# no.net
KiCad netlist of a schematic drawn in Altium Designer
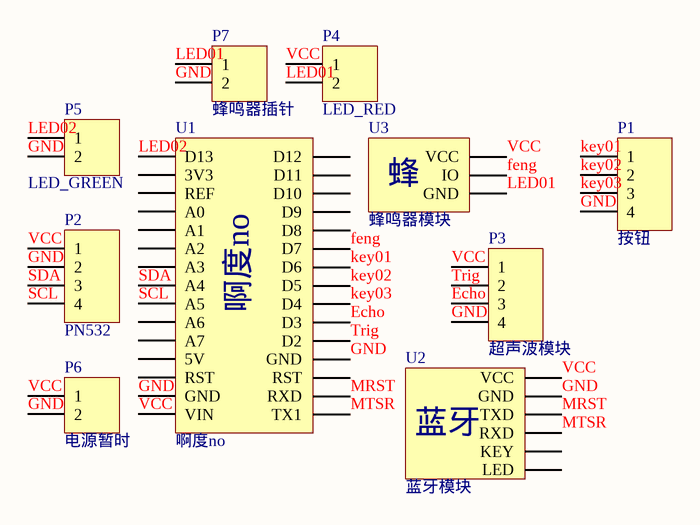
[diagram p0: 啊度no.SchDoc]

(export (version "E")
  (design (tool "Eeschema 10.0.6"))
  (components
    (comp (ref "P1")
      (value "按钮")
      (footprint "HDR1X4")
      (description "Header, 4-Pin")
      (fields (field (name "PUBLISHER") "Altium Limited"))
      (libsource (lib "Miscellaneous Connectors") (part "Header 4"))
    )
    (comp (ref "P2")
      (value "PN532")
      (footprint "HDR1X4")
      (description "Header, 4-Pin")
      (fields (field (name "PUBLISHER") "Altium Limited"))
      (libsource (lib "Miscellaneous Connectors") (part "Header 4"))
    )
    (comp (ref "P3")
      (value "超声波模块")
      (footprint "HDR1X4")
      (description "Header, 4-Pin")
      (fields (field (name "PUBLISHER") "Altium Limited"))
      (libsource (lib "Miscellaneous Connectors") (part "Header 4"))
    )
    (comp (ref "P4")
      (value "LED_RED")
      (footprint "HDR1X2")
      (description "Header, 2-Pin")
      (fields (field (name "PUBLISHER") "Altium Limited"))
      (libsource (lib "Miscellaneous Connectors") (part "Header 2"))
    )
    (comp (ref "P5")
      (value "LED_GREEN")
      (footprint "HDR1X2")
      (description "Header, 2-Pin")
      (fields (field (name "PUBLISHER") "Altium Limited"))
      (libsource (lib "Miscellaneous Connectors") (part "Header 2"))
    )
    (comp (ref "P6")
      (value "电源暂时")
      (footprint "HDR1X2")
      (description "Header, 2-Pin")
      (fields (field (name "PUBLISHER") "Altium Limited"))
      (libsource (lib "Miscellaneous Connectors") (part "Header 2"))
    )
    (comp (ref "P7")
      (value "蜂鸣器插针")
      (footprint "HDR1X2")
      (description "Header, 2-Pin")
      (fields (field (name "PUBLISHER") "Altium Limited"))
      (libsource (lib "Miscellaneous Connectors") (part "Header 2"))
    )
    (comp (ref "U1") (value "啊度no") (footprint "啊度no") (libsource (lib "元件库编号001") (part "啊度no")))
    (comp (ref "U2") (value "蓝牙模块") (footprint "蓝牙模块") (libsource (lib "元件库编号001") (part "蓝牙模块")))
    (comp (ref "U3") (value "蜂鸣器模块") (footprint "蜂鸣器模块") (libsource (lib "元件库编号001") (part "蜂鸣器模块")))
  )
  (nets
    (net (code "1") (name "/Echo") (class "Default")
      (node (ref "P3") (pin "3") (pinfunction "3_3") (pintype "passive"))
      (node (ref "U1") (pin "D3") (pinfunction "D3_D3") (pintype "passive"))
    )
    (net (code "2") (name "/GND") (class "Default")
      (node (ref "P1") (pin "4") (pinfunction "4_4") (pintype "passive"))
      (node (ref "P2") (pin "2") (pinfunction "2_2") (pintype "passive"))
      (node (ref "P3") (pin "4") (pinfunction "4_4") (pintype "passive"))
      (node (ref "P5") (pin "2") (pinfunction "2_2") (pintype "passive"))
      (node (ref "P6") (pin "2") (pinfunction "2_2") (pintype "passive"))
      (node (ref "P7") (pin "2") (pinfunction "2_2") (pintype "passive"))
      (node (ref "U1") (pin "GND") (pinfunction "GND_GND") (pintype "passive"))
      (node (ref "U2") (pin "GND") (pinfunction "GND_GND") (pintype "passive"))
    )
    (net (code "3") (name "/LED01") (class "Default")
      (node (ref "P4") (pin "2") (pinfunction "2_2") (pintype "passive"))
      (node (ref "P7") (pin "1") (pinfunction "1_1") (pintype "passive"))
      (node (ref "U3") (pin "GND") (pinfunction "GND_GND") (pintype "passive"))
    )
    (net (code "4") (name "/LED02") (class "Default")
      (node (ref "P5") (pin "1") (pinfunction "1_1") (pintype "passive"))
      (node (ref "U1") (pin "D13") (pinfunction "D13_D13") (pintype "passive"))
    )
    (net (code "5") (name "/MRST") (class "Default")
      (node (ref "U1") (pin "RXD") (pinfunction "RXD_RXD") (pintype "passive"))
      (node (ref "U2") (pin "TXD") (pinfunction "TXD_TXD") (pintype "passive"))
    )
    (net (code "6") (name "/MTSR") (class "Default")
      (node (ref "U1") (pin "TX1") (pinfunction "TX1_TX1") (pintype "passive"))
      (node (ref "U2") (pin "RXD") (pinfunction "RXD_RXD") (pintype "passive"))
    )
    (net (code "7") (name "/SCL") (class "Default")
      (node (ref "P2") (pin "4") (pinfunction "4_4") (pintype "passive"))
      (node (ref "U1") (pin "A5") (pinfunction "A5_A5") (pintype "passive"))
    )
    (net (code "8") (name "/SDA") (class "Default")
      (node (ref "P2") (pin "3") (pinfunction "3_3") (pintype "passive"))
      (node (ref "U1") (pin "A4") (pinfunction "A4_A4") (pintype "passive"))
    )
    (net (code "9") (name "/Trig") (class "Default")
      (node (ref "P3") (pin "2") (pinfunction "2_2") (pintype "passive"))
      (node (ref "U1") (pin "D2") (pinfunction "D2_D2") (pintype "passive"))
    )
    (net (code "10") (name "/VCC") (class "Default")
      (node (ref "P2") (pin "1") (pinfunction "1_1") (pintype "passive"))
      (node (ref "P3") (pin "1") (pinfunction "1_1") (pintype "passive"))
      (node (ref "P4") (pin "1") (pinfunction "1_1") (pintype "passive"))
      (node (ref "P6") (pin "1") (pinfunction "1_1") (pintype "passive"))
      (node (ref "U1") (pin "VIN") (pinfunction "VIN_VIN") (pintype "passive"))
      (node (ref "U2") (pin "VCC") (pinfunction "VCC_VCC") (pintype "passive"))
      (node (ref "U3") (pin "VCC") (pinfunction "VCC_VCC") (pintype "passive"))
    )
    (net (code "11") (name "/feng") (class "Default")
      (node (ref "U1") (pin "D7") (pinfunction "D7_D7") (pintype "passive"))
      (node (ref "U3") (pin "IO") (pinfunction "IO_IO") (pintype "passive"))
    )
    (net (code "12") (name "/key01") (class "Default")
      (node (ref "P1") (pin "1") (pinfunction "1_1") (pintype "passive"))
      (node (ref "U1") (pin "D6") (pinfunction "D6_D6") (pintype "passive"))
    )
    (net (code "13") (name "/key02") (class "Default")
      (node (ref "P1") (pin "2") (pinfunction "2_2") (pintype "passive"))
      (node (ref "U1") (pin "D5") (pinfunction "D5_D5") (pintype "passive"))
    )
    (net (code "14") (name "/key03") (class "Default")
      (node (ref "P1") (pin "3") (pinfunction "3_3") (pintype "passive"))
      (node (ref "U1") (pin "D4") (pinfunction "D4_D4") (pintype "passive"))
    )
    (net (code "15") (name "unconnected-(U1-Pad3V3)") (class "Default")
      (node (ref "U1") (pin "3V3") (pinfunction "3V3_3V3") (pintype "passive"))
    )
    (net (code "16") (name "unconnected-(U1-Pad5V)") (class "Default")
      (node (ref "U1") (pin "5V") (pinfunction "5V_5V") (pintype "passive"))
    )
    (net (code "17") (name "unconnected-(U1-PadA0)") (class "Default")
      (node (ref "U1") (pin "A0") (pinfunction "A0_A0") (pintype "passive"))
    )
    (net (code "18") (name "unconnected-(U1-PadA1)") (class "Default")
      (node (ref "U1") (pin "A1") (pinfunction "A1_A1") (pintype "passive"))
    )
    (net (code "19") (name "unconnected-(U1-PadA2)") (class "Default")
      (node (ref "U1") (pin "A2") (pinfunction "A2_A2") (pintype "passive"))
    )
    (net (code "20") (name "unconnected-(U1-PadA3)") (class "Default")
      (node (ref "U1") (pin "A3") (pinfunction "A3_A3") (pintype "passive"))
    )
    (net (code "21") (name "unconnected-(U1-PadA6)") (class "Default")
      (node (ref "U1") (pin "A6") (pinfunction "A6_A6") (pintype "passive"))
    )
    (net (code "22") (name "unconnected-(U1-PadA7)") (class "Default")
      (node (ref "U1") (pin "A7") (pinfunction "A7_A7") (pintype "passive"))
    )
    (net (code "23") (name "unconnected-(U1-PadD8)") (class "Default")
      (node (ref "U1") (pin "D8") (pinfunction "D8_D8") (pintype "passive"))
    )
    (net (code "24") (name "unconnected-(U1-PadD9)") (class "Default")
      (node (ref "U1") (pin "D9") (pinfunction "D9_D9") (pintype "passive"))
    )
    (net (code "25") (name "unconnected-(U1-PadD10)") (class "Default")
      (node (ref "U1") (pin "D10") (pinfunction "D10_D10") (pintype "passive"))
    )
    (net (code "26") (name "unconnected-(U1-PadD11)") (class "Default")
      (node (ref "U1") (pin "D11") (pinfunction "D11_D11") (pintype "passive"))
    )
    (net (code "27") (name "unconnected-(U1-PadD12)") (class "Default")
      (node (ref "U1") (pin "D12") (pinfunction "D12_D12") (pintype "passive"))
    )
    (net (code "28") (name "unconnected-(U1-PadREF)") (class "Default")
      (node (ref "U1") (pin "REF") (pinfunction "REF_REF") (pintype "passive"))
    )
    (net (code "29") (name "unconnected-(U1-PadRST)") (class "Default")
      (node (ref "U1") (pin "RST") (pinfunction "RST_RST") (pintype "passive"))
    )
    (net (code "30") (name "unconnected-(U1-PadRST)_1") (class "Default")
      (node (ref "U1") (pin "RST") (pinfunction "RST_RST") (pintype "passive"))
    )
    (net (code "31") (name "unconnected-(U2-PadKEY)") (class "Default")
      (node (ref "U2") (pin "KEY") (pinfunction "KEY_KEY") (pintype "passive"))
    )
    (net (code "32") (name "unconnected-(U2-PadLED)") (class "Default")
      (node (ref "U2") (pin "LED") (pinfunction "LED_LED") (pintype "passive"))
    )
  )
)
